# ESC_logic.net
KiCad netlist of a schematic drawn in EAGLE
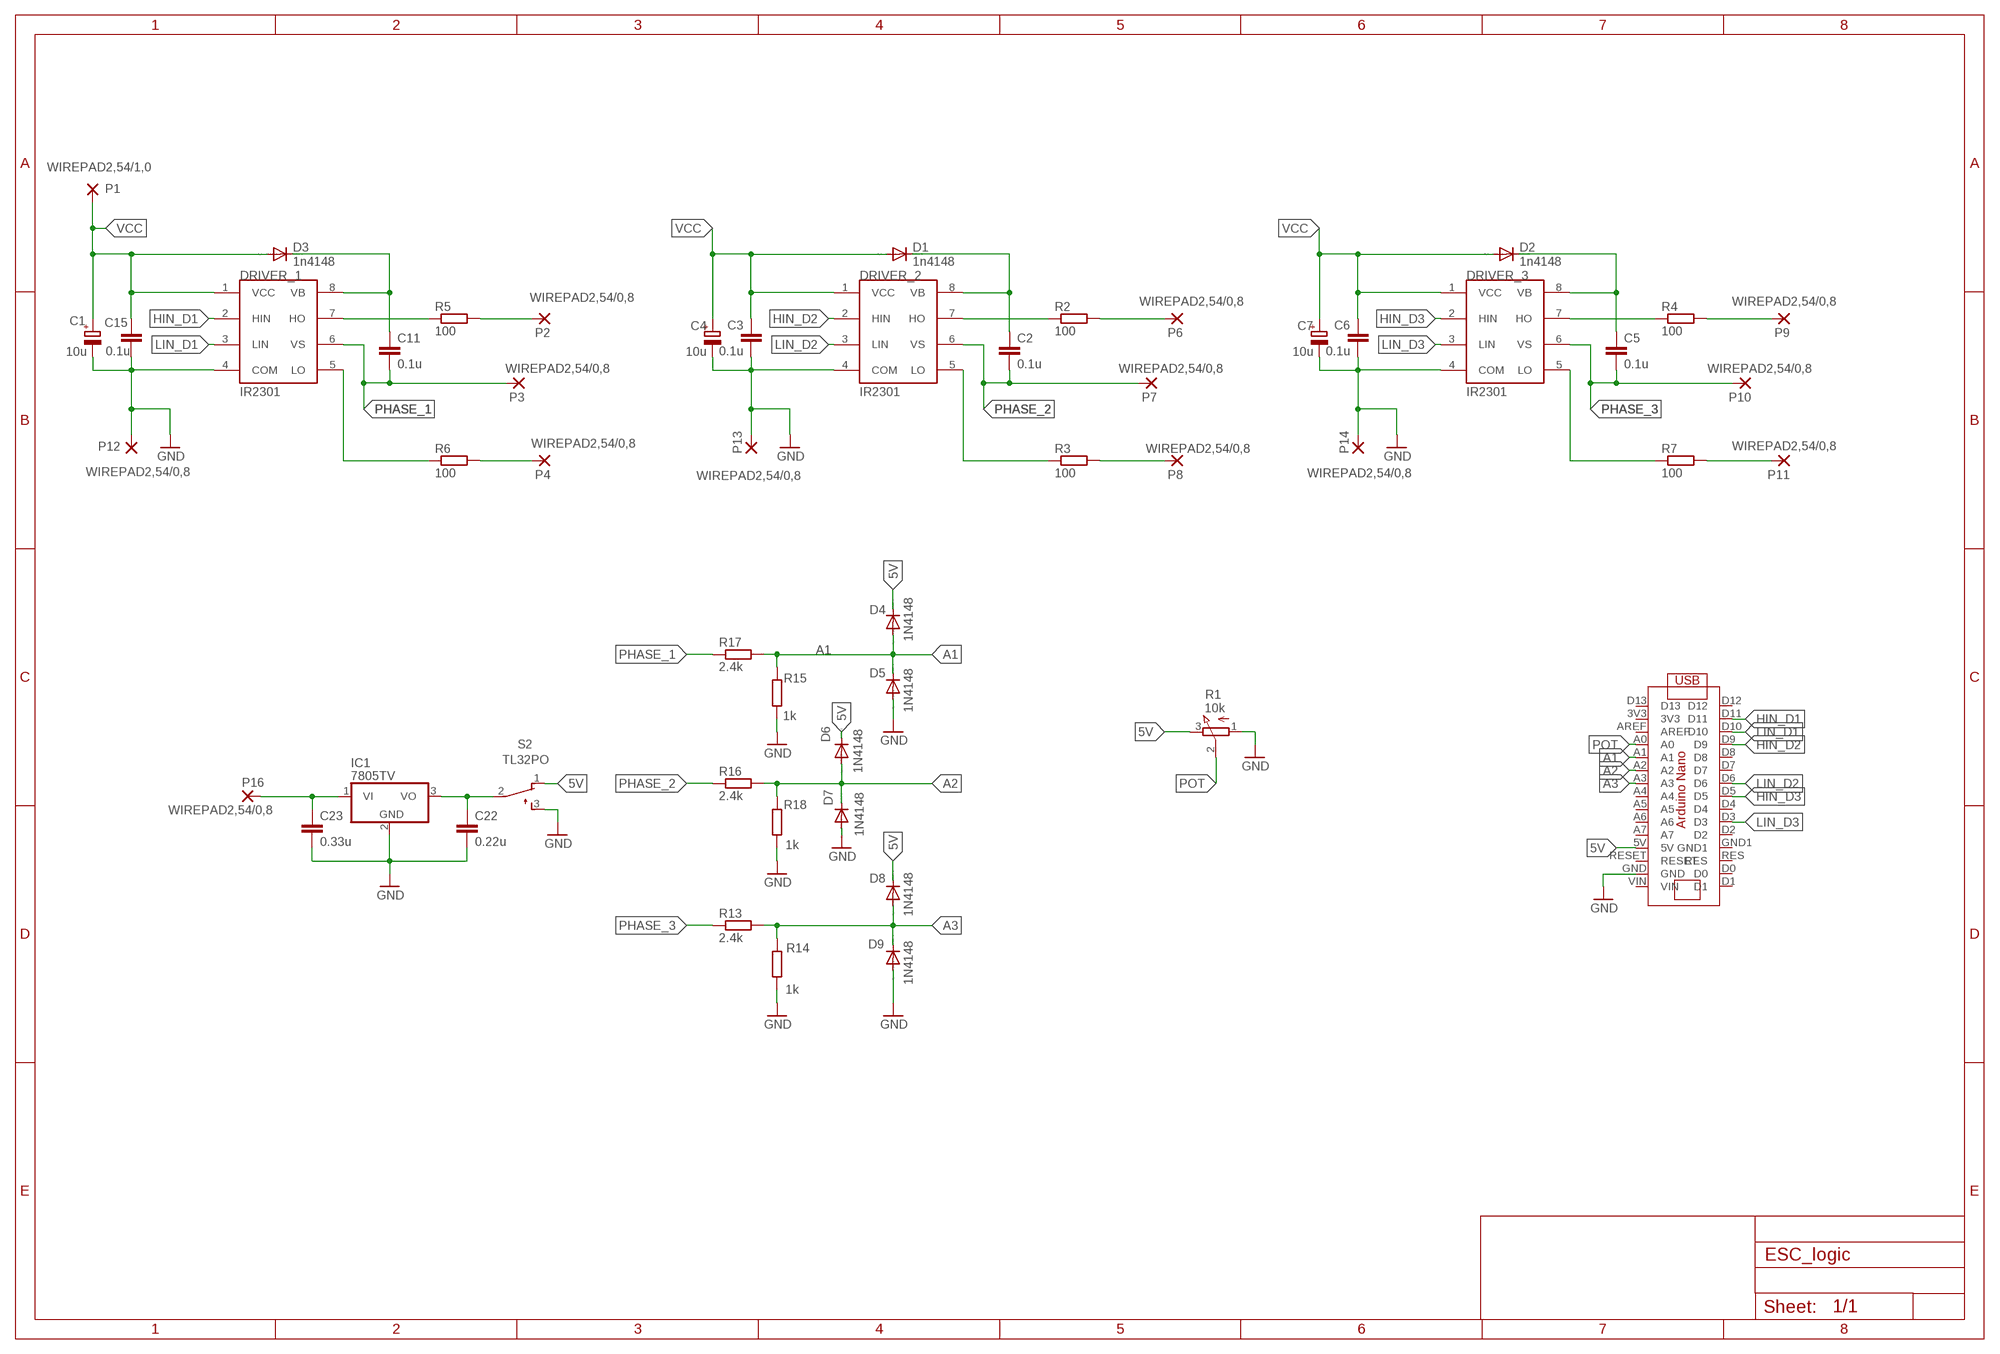
[diagram p0: schematic, sheet 1]

(export (version "E")
  (design (tool "Eeschema 10.0.6"))
  (components
    (comp (ref "C1")
      (value "10u")
      (footprint "eagle-import:153CLV-0605")
      (libsource (lib "eagle-import") (part "CPOL-EU153CLV-0605"))
    )
    (comp (ref "C2")
      (value "0.1u")
      (footprint "eagle-import:C1206")
      (libsource (lib "eagle-import") (part "CC1206"))
    )
    (comp (ref "C3")
      (value "0.1u")
      (footprint "eagle-import:C1206")
      (libsource (lib "eagle-import") (part "CC1206"))
    )
    (comp (ref "C4")
      (value "10u")
      (footprint "eagle-import:153CLV-0605")
      (libsource (lib "eagle-import") (part "CPOL-EU153CLV-0605"))
    )
    (comp (ref "C5")
      (value "0.1u")
      (footprint "eagle-import:C1206")
      (libsource (lib "eagle-import") (part "CC1206"))
    )
    (comp (ref "C6")
      (value "0.1u")
      (footprint "eagle-import:C1206")
      (libsource (lib "eagle-import") (part "CC1206"))
    )
    (comp (ref "C7")
      (value "10u")
      (footprint "eagle-import:153CLV-0605")
      (libsource (lib "eagle-import") (part "CPOL-EU153CLV-0605"))
    )
    (comp (ref "C11")
      (value "0.1u")
      (footprint "eagle-import:C1206")
      (libsource (lib "eagle-import") (part "CC1206"))
    )
    (comp (ref "C15")
      (value "0.1u")
      (footprint "eagle-import:C1206")
      (libsource (lib "eagle-import") (part "CC1206"))
    )
    (comp (ref "C22")
      (value "0.22u")
      (footprint "eagle-import:C1206")
      (libsource (lib "eagle-import") (part "CC1206"))
    )
    (comp (ref "C23")
      (value "0.33u")
      (footprint "eagle-import:C1206")
      (libsource (lib "eagle-import") (part "CC1206"))
    )
    (comp (ref "D1")
      (value "1n4148")
      (footprint "eagle-import:DO41-10")
      (libsource (lib "eagle-import") (part "DIODE-DO41-10"))
    )
    (comp (ref "D2")
      (value "1n4148")
      (footprint "eagle-import:DO41-10")
      (libsource (lib "eagle-import") (part "DIODE-DO41-10"))
    )
    (comp (ref "D3")
      (value "1n4148")
      (footprint "eagle-import:DO41-10")
      (libsource (lib "eagle-import") (part "DIODE-DO41-10"))
    )
    (comp (ref "D4")
      (value "1N4148")
      (footprint "eagle-import:DO41-10")
      (libsource (lib "eagle-import") (part "DIODE-DO41-10"))
    )
    (comp (ref "D5")
      (value "1N4148")
      (footprint "eagle-import:DO41-10")
      (libsource (lib "eagle-import") (part "DIODE-DO41-10"))
    )
    (comp (ref "D6")
      (value "1N4148")
      (footprint "eagle-import:DO41-10")
      (libsource (lib "eagle-import") (part "DIODE-DO41-10"))
    )
    (comp (ref "D7")
      (value "1N4148")
      (footprint "eagle-import:DO41-10")
      (libsource (lib "eagle-import") (part "DIODE-DO41-10"))
    )
    (comp (ref "D8")
      (value "1N4148")
      (footprint "eagle-import:DO41-10")
      (libsource (lib "eagle-import") (part "DIODE-DO41-10"))
    )
    (comp (ref "D9")
      (value "1N4148")
      (footprint "eagle-import:DO41-10")
      (libsource (lib "eagle-import") (part "DIODE-DO41-10"))
    )
    (comp (ref "DRIVER_1")
      (value "IR2301")
      (footprint "eagle-import:DIL08")
      (fields (field (name "MF") "Infineon"))
      (libsource (lib "eagle-import") (part "IR2301"))
    )
    (comp (ref "DRIVER_2")
      (value "IR2301")
      (footprint "eagle-import:DIL08")
      (fields (field (name "MF") "Infineon"))
      (libsource (lib "eagle-import") (part "IR2301"))
    )
    (comp (ref "DRIVER_3")
      (value "IR2301")
      (footprint "eagle-import:DIL08")
      (fields (field (name "MF") "Infineon"))
      (libsource (lib "eagle-import") (part "IR2301"))
    )
    (comp (ref "IC1")
      (value "7805TV")
      (footprint "eagle-import:TO220V")
      (libsource (lib "eagle-import") (part "78TV05"))
    )
    (comp (ref "P1")
      (value "WIREPAD2,54/1,0")
      (footprint "eagle-import:2,54_1,0")
      (libsource (lib "eagle-import") (part "WIREPAD2,54/1,0"))
    )
    (comp (ref "P2")
      (value "WIREPAD2,54/0,8")
      (footprint "eagle-import:2,54_0,8")
      (libsource (lib "eagle-import") (part "WIREPAD2,54/0,8"))
    )
    (comp (ref "P3")
      (value "WIREPAD2,54/0,8")
      (footprint "eagle-import:2,54_0,8")
      (libsource (lib "eagle-import") (part "WIREPAD2,54/0,8"))
    )
    (comp (ref "P4")
      (value "WIREPAD2,54/0,8")
      (footprint "eagle-import:2,54_0,8")
      (libsource (lib "eagle-import") (part "WIREPAD2,54/0,8"))
    )
    (comp (ref "P6")
      (value "WIREPAD2,54/0,8")
      (footprint "eagle-import:2,54_0,8")
      (libsource (lib "eagle-import") (part "WIREPAD2,54/0,8"))
    )
    (comp (ref "P7")
      (value "WIREPAD2,54/0,8")
      (footprint "eagle-import:2,54_0,8")
      (libsource (lib "eagle-import") (part "WIREPAD2,54/0,8"))
    )
    (comp (ref "P8")
      (value "WIREPAD2,54/0,8")
      (footprint "eagle-import:2,54_0,8")
      (libsource (lib "eagle-import") (part "WIREPAD2,54/0,8"))
    )
    (comp (ref "P9")
      (value "WIREPAD2,54/0,8")
      (footprint "eagle-import:2,54_0,8")
      (libsource (lib "eagle-import") (part "WIREPAD2,54/0,8"))
    )
    (comp (ref "P10")
      (value "WIREPAD2,54/0,8")
      (footprint "eagle-import:2,54_0,8")
      (libsource (lib "eagle-import") (part "WIREPAD2,54/0,8"))
    )
    (comp (ref "P11")
      (value "WIREPAD2,54/0,8")
      (footprint "eagle-import:2,54_0,8")
      (libsource (lib "eagle-import") (part "WIREPAD2,54/0,8"))
    )
    (comp (ref "P12")
      (value "WIREPAD2,54/0,8")
      (footprint "eagle-import:2,54_0,8")
      (libsource (lib "eagle-import") (part "WIREPAD2,54/0,8"))
    )
    (comp (ref "P13")
      (value "WIREPAD2,54/0,8")
      (footprint "eagle-import:2,54_0,8")
      (libsource (lib "eagle-import") (part "WIREPAD2,54/0,8"))
    )
    (comp (ref "P14")
      (value "WIREPAD2,54/0,8")
      (footprint "eagle-import:2,54_0,8")
      (libsource (lib "eagle-import") (part "WIREPAD2,54/0,8"))
    )
    (comp (ref "P16")
      (value "WIREPAD2,54/0,8")
      (footprint "eagle-import:2,54_0,8")
      (libsource (lib "eagle-import") (part "WIREPAD2,54/0,8"))
    )
    (comp (ref "R1")
      (value "10k")
      (footprint "eagle-import:3RP_1610N")
      (libsource (lib "eagle-import") (part "3RP/1610N"))
    )
    (comp (ref "R2")
      (value "100")
      (footprint "eagle-import:R1206")
      (libsource (lib "eagle-import") (part "R-EU_R1206"))
    )
    (comp (ref "R3")
      (value "100")
      (footprint "eagle-import:R1206")
      (libsource (lib "eagle-import") (part "R-EU_R1206"))
    )
    (comp (ref "R4")
      (value "100")
      (footprint "eagle-import:R1206")
      (libsource (lib "eagle-import") (part "R-EU_R1206"))
    )
    (comp (ref "R5")
      (value "100")
      (footprint "eagle-import:R1206")
      (libsource (lib "eagle-import") (part "R-EU_R1206"))
    )
    (comp (ref "R6")
      (value "100")
      (footprint "eagle-import:R1206")
      (libsource (lib "eagle-import") (part "R-EU_R1206"))
    )
    (comp (ref "R7")
      (value "100")
      (footprint "eagle-import:R1206")
      (libsource (lib "eagle-import") (part "R-EU_R1206"))
    )
    (comp (ref "R13")
      (value "2.4k")
      (footprint "eagle-import:R1206")
      (libsource (lib "eagle-import") (part "R-EU_R1206"))
    )
    (comp (ref "R14")
      (value "1k")
      (footprint "eagle-import:R1206")
      (libsource (lib "eagle-import") (part "R-EU_R1206"))
    )
    (comp (ref "R15")
      (value "1k")
      (footprint "eagle-import:R1206")
      (libsource (lib "eagle-import") (part "R-EU_R1206"))
    )
    (comp (ref "R16")
      (value "2.4k")
      (footprint "eagle-import:R1206")
      (libsource (lib "eagle-import") (part "R-EU_R1206"))
    )
    (comp (ref "R17")
      (value "2.4k")
      (footprint "eagle-import:R1206")
      (libsource (lib "eagle-import") (part "R-EU_R1206"))
    )
    (comp (ref "R18")
      (value "1k")
      (footprint "eagle-import:R1206")
      (libsource (lib "eagle-import") (part "R-EU_R1206"))
    )
    (comp (ref "S2")
      (value "TL32PO")
      (footprint "eagle-import:TL3XPO")
      (libsource (lib "eagle-import") (part "TL32PO"))
    )
    (comp (ref "U$7")
      (value "ARDUINO-NANO")
      (footprint "eagle-import:ARDUINO-NANO")
      (libsource (lib "eagle-import") (part "ARDUINO-NANO"))
    )
  )
  (nets
    (net (code "1") (name "5V") (class "Default")
      (node (ref "D4") (pin "C") (pinfunction "C_C") (pintype "passive"))
      (node (ref "D6") (pin "C") (pinfunction "C_C") (pintype "passive"))
      (node (ref "D8") (pin "C") (pinfunction "C_C") (pintype "passive"))
      (node (ref "R1") (pin "3") (pinfunction "E_3") (pintype "passive"))
      (node (ref "S2") (pin "1") (pinfunction "O_1") (pintype "passive"))
      (node (ref "U$7") (pin "5V") (pinfunction "5V_5V") (pintype "bidirectional"))
    )
    (net (code "2") (name "A1") (class "Default")
      (node (ref "D4") (pin "A") (pinfunction "A_A") (pintype "passive"))
      (node (ref "D5") (pin "C") (pinfunction "C_C") (pintype "passive"))
      (node (ref "R15") (pin "2") (pinfunction "2_2") (pintype "bidirectional"))
      (node (ref "R17") (pin "2") (pinfunction "2_2") (pintype "bidirectional"))
      (node (ref "U$7") (pin "A1") (pinfunction "A1_A1") (pintype "bidirectional"))
    )
    (net (code "3") (name "A2") (class "Default")
      (node (ref "D6") (pin "A") (pinfunction "A_A") (pintype "passive"))
      (node (ref "D7") (pin "C") (pinfunction "C_C") (pintype "passive"))
      (node (ref "R16") (pin "2") (pinfunction "2_2") (pintype "bidirectional"))
      (node (ref "R18") (pin "2") (pinfunction "2_2") (pintype "bidirectional"))
      (node (ref "U$7") (pin "A2") (pinfunction "A2_A2") (pintype "bidirectional"))
    )
    (net (code "4") (name "A3") (class "Default")
      (node (ref "D8") (pin "A") (pinfunction "A_A") (pintype "passive"))
      (node (ref "D9") (pin "C") (pinfunction "C_C") (pintype "passive"))
      (node (ref "R13") (pin "2") (pinfunction "2_2") (pintype "bidirectional"))
      (node (ref "R14") (pin "2") (pinfunction "2_2") (pintype "bidirectional"))
      (node (ref "U$7") (pin "A3") (pinfunction "A3_A3") (pintype "bidirectional"))
    )
    (net (code "5") (name "GND") (class "Default")
      (node (ref "C1") (pin "-") (pinfunction "-_-") (pintype "passive"))
      (node (ref "C15") (pin "2") (pinfunction "2_2") (pintype "passive"))
      (node (ref "C22") (pin "2") (pinfunction "2_2") (pintype "passive"))
      (node (ref "C23") (pin "2") (pinfunction "2_2") (pintype "passive"))
      (node (ref "C3") (pin "2") (pinfunction "2_2") (pintype "passive"))
      (node (ref "C4") (pin "-") (pinfunction "-_-") (pintype "passive"))
      (node (ref "C6") (pin "2") (pinfunction "2_2") (pintype "passive"))
      (node (ref "C7") (pin "-") (pinfunction "-_-") (pintype "passive"))
      (node (ref "D5") (pin "A") (pinfunction "A_A") (pintype "passive"))
      (node (ref "D7") (pin "A") (pinfunction "A_A") (pintype "passive"))
      (node (ref "D9") (pin "A") (pinfunction "A_A") (pintype "passive"))
      (node (ref "DRIVER_1") (pin "4") (pinfunction "COM_4") (pintype "power_in"))
      (node (ref "DRIVER_2") (pin "4") (pinfunction "COM_4") (pintype "power_in"))
      (node (ref "DRIVER_3") (pin "4") (pinfunction "COM_4") (pintype "power_in"))
      (node (ref "IC1") (pin "2") (pinfunction "GND_2") (pintype "passive"))
      (node (ref "P12") (pin "1") (pinfunction "P_1") (pintype "passive"))
      (node (ref "P13") (pin "1") (pinfunction "P_1") (pintype "passive"))
      (node (ref "P14") (pin "1") (pinfunction "P_1") (pintype "passive"))
      (node (ref "R1") (pin "1") (pinfunction "A_1") (pintype "passive"))
      (node (ref "R14") (pin "1") (pinfunction "1_1") (pintype "bidirectional"))
      (node (ref "R15") (pin "1") (pinfunction "1_1") (pintype "bidirectional"))
      (node (ref "R18") (pin "1") (pinfunction "1_1") (pintype "bidirectional"))
      (node (ref "S2") (pin "3") (pinfunction "S_3") (pintype "passive"))
      (node (ref "U$7") (pin "GND") (pinfunction "GND_GND") (pintype "bidirectional"))
    )
    (net (code "6") (name "HIN_D1") (class "Default")
      (node (ref "DRIVER_1") (pin "2") (pinfunction "HIN_2") (pintype "input"))
      (node (ref "U$7") (pin "D11") (pinfunction "D11_D11") (pintype "bidirectional"))
    )
    (net (code "7") (name "HIN_D2") (class "Default")
      (node (ref "DRIVER_2") (pin "2") (pinfunction "HIN_2") (pintype "input"))
      (node (ref "U$7") (pin "D9") (pinfunction "D9_D9") (pintype "bidirectional"))
    )
    (net (code "8") (name "HIN_D3") (class "Default")
      (node (ref "DRIVER_3") (pin "2") (pinfunction "HIN_2") (pintype "input"))
      (node (ref "U$7") (pin "D5") (pinfunction "D5_D5") (pintype "bidirectional"))
    )
    (net (code "9") (name "LIN_D1") (class "Default")
      (node (ref "DRIVER_1") (pin "3") (pinfunction "LIN_3") (pintype "input"))
      (node (ref "U$7") (pin "D10") (pinfunction "D10_D10") (pintype "bidirectional"))
    )
    (net (code "10") (name "LIN_D2") (class "Default")
      (node (ref "DRIVER_2") (pin "3") (pinfunction "LIN_3") (pintype "input"))
      (node (ref "U$7") (pin "D6") (pinfunction "D6_D6") (pintype "bidirectional"))
    )
    (net (code "11") (name "LIN_D3") (class "Default")
      (node (ref "DRIVER_3") (pin "3") (pinfunction "LIN_3") (pintype "input"))
      (node (ref "U$7") (pin "D3") (pinfunction "D3_D3") (pintype "bidirectional"))
    )
    (net (code "12") (name "Net-(DRIVER_1-HO)") (class "Default")
      (node (ref "DRIVER_1") (pin "7") (pinfunction "HO_7") (pintype "output"))
      (node (ref "R5") (pin "1") (pinfunction "1_1") (pintype "bidirectional"))
    )
    (net (code "13") (name "Net-(DRIVER_1-LO)") (class "Default")
      (node (ref "DRIVER_1") (pin "5") (pinfunction "LO_5") (pintype "output"))
      (node (ref "R6") (pin "1") (pinfunction "1_1") (pintype "bidirectional"))
    )
    (net (code "14") (name "Net-(DRIVER_1-VB)") (class "Default")
      (node (ref "C11") (pin "1") (pinfunction "1_1") (pintype "passive"))
      (node (ref "D3") (pin "C") (pinfunction "C_C") (pintype "passive"))
      (node (ref "DRIVER_1") (pin "8") (pinfunction "VB_8") (pintype "power_in"))
    )
    (net (code "15") (name "Net-(DRIVER_2-HO)") (class "Default")
      (node (ref "DRIVER_2") (pin "7") (pinfunction "HO_7") (pintype "output"))
      (node (ref "R2") (pin "1") (pinfunction "1_1") (pintype "bidirectional"))
    )
    (net (code "16") (name "Net-(DRIVER_2-LO)") (class "Default")
      (node (ref "DRIVER_2") (pin "5") (pinfunction "LO_5") (pintype "output"))
      (node (ref "R3") (pin "1") (pinfunction "1_1") (pintype "bidirectional"))
    )
    (net (code "17") (name "Net-(DRIVER_2-VB)") (class "Default")
      (node (ref "C2") (pin "1") (pinfunction "1_1") (pintype "passive"))
      (node (ref "D1") (pin "C") (pinfunction "C_C") (pintype "passive"))
      (node (ref "DRIVER_2") (pin "8") (pinfunction "VB_8") (pintype "power_in"))
    )
    (net (code "18") (name "Net-(DRIVER_3-HO)") (class "Default")
      (node (ref "DRIVER_3") (pin "7") (pinfunction "HO_7") (pintype "output"))
      (node (ref "R4") (pin "1") (pinfunction "1_1") (pintype "bidirectional"))
    )
    (net (code "19") (name "Net-(DRIVER_3-LO)") (class "Default")
      (node (ref "DRIVER_3") (pin "5") (pinfunction "LO_5") (pintype "output"))
      (node (ref "R7") (pin "1") (pinfunction "1_1") (pintype "bidirectional"))
    )
    (net (code "20") (name "Net-(DRIVER_3-VB)") (class "Default")
      (node (ref "C5") (pin "1") (pinfunction "1_1") (pintype "passive"))
      (node (ref "D2") (pin "C") (pinfunction "C_C") (pintype "passive"))
      (node (ref "DRIVER_3") (pin "8") (pinfunction "VB_8") (pintype "power_in"))
    )
    (net (code "21") (name "Net-(IC1-VI)") (class "Default")
      (node (ref "C23") (pin "1") (pinfunction "1_1") (pintype "passive"))
      (node (ref "IC1") (pin "1") (pinfunction "VI_1") (pintype "input"))
      (node (ref "P16") (pin "1") (pinfunction "P_1") (pintype "passive"))
    )
    (net (code "22") (name "Net-(IC1-VO)") (class "Default")
      (node (ref "C22") (pin "1") (pinfunction "1_1") (pintype "passive"))
      (node (ref "IC1") (pin "3") (pinfunction "VO_3") (pintype "passive"))
      (node (ref "S2") (pin "2") (pinfunction "P_2") (pintype "passive"))
    )
    (net (code "23") (name "Net-(P2-P)") (class "Default")
      (node (ref "P2") (pin "1") (pinfunction "P_1") (pintype "passive"))
      (node (ref "R5") (pin "2") (pinfunction "2_2") (pintype "bidirectional"))
    )
    (net (code "24") (name "Net-(P4-P)") (class "Default")
      (node (ref "P4") (pin "1") (pinfunction "P_1") (pintype "passive"))
      (node (ref "R6") (pin "2") (pinfunction "2_2") (pintype "bidirectional"))
    )
    (net (code "25") (name "Net-(P6-P)") (class "Default")
      (node (ref "P6") (pin "1") (pinfunction "P_1") (pintype "passive"))
      (node (ref "R2") (pin "2") (pinfunction "2_2") (pintype "bidirectional"))
    )
    (net (code "26") (name "Net-(P8-P)") (class "Default")
      (node (ref "P8") (pin "1") (pinfunction "P_1") (pintype "passive"))
      (node (ref "R3") (pin "2") (pinfunction "2_2") (pintype "bidirectional"))
    )
    (net (code "27") (name "Net-(P9-P)") (class "Default")
      (node (ref "P9") (pin "1") (pinfunction "P_1") (pintype "passive"))
      (node (ref "R4") (pin "2") (pinfunction "2_2") (pintype "bidirectional"))
    )
    (net (code "28") (name "Net-(P11-P)") (class "Default")
      (node (ref "P11") (pin "1") (pinfunction "P_1") (pintype "passive"))
      (node (ref "R7") (pin "2") (pinfunction "2_2") (pintype "bidirectional"))
    )
    (net (code "29") (name "PHASE_1") (class "Default")
      (node (ref "C11") (pin "2") (pinfunction "2_2") (pintype "passive"))
      (node (ref "DRIVER_1") (pin "6") (pinfunction "VS_6") (pintype "output"))
      (node (ref "P3") (pin "1") (pinfunction "P_1") (pintype "passive"))
      (node (ref "R17") (pin "1") (pinfunction "1_1") (pintype "bidirectional"))
    )
    (net (code "30") (name "PHASE_2") (class "Default")
      (node (ref "C2") (pin "2") (pinfunction "2_2") (pintype "passive"))
      (node (ref "DRIVER_2") (pin "6") (pinfunction "VS_6") (pintype "output"))
      (node (ref "P7") (pin "1") (pinfunction "P_1") (pintype "passive"))
      (node (ref "R16") (pin "1") (pinfunction "1_1") (pintype "bidirectional"))
    )
    (net (code "31") (name "PHASE_3") (class "Default")
      (node (ref "C5") (pin "2") (pinfunction "2_2") (pintype "passive"))
      (node (ref "DRIVER_3") (pin "6") (pinfunction "VS_6") (pintype "output"))
      (node (ref "P10") (pin "1") (pinfunction "P_1") (pintype "passive"))
      (node (ref "R13") (pin "1") (pinfunction "1_1") (pintype "bidirectional"))
    )
    (net (code "32") (name "POT") (class "Default")
      (node (ref "R1") (pin "2") (pinfunction "S_2") (pintype "passive"))
      (node (ref "U$7") (pin "A0") (pinfunction "A0_A0") (pintype "bidirectional"))
    )
    (net (code "33") (name "VCC") (class "Default")
      (node (ref "C1") (pin "+") (pinfunction "+_+") (pintype "passive"))
      (node (ref "C15") (pin "1") (pinfunction "1_1") (pintype "passive"))
      (node (ref "C3") (pin "1") (pinfunction "1_1") (pintype "passive"))
      (node (ref "C4") (pin "+") (pinfunction "+_+") (pintype "passive"))
      (node (ref "C6") (pin "1") (pinfunction "1_1") (pintype "passive"))
      (node (ref "C7") (pin "+") (pinfunction "+_+") (pintype "passive"))
      (node (ref "D1") (pin "A") (pinfunction "A_A") (pintype "passive"))
      (node (ref "D2") (pin "A") (pinfunction "A_A") (pintype "passive"))
      (node (ref "D3") (pin "A") (pinfunction "A_A") (pintype "passive"))
      (node (ref "DRIVER_1") (pin "1") (pinfunction "VCC_1") (pintype "power_in"))
      (node (ref "DRIVER_2") (pin "1") (pinfunction "VCC_1") (pintype "power_in"))
      (node (ref "DRIVER_3") (pin "1") (pinfunction "VCC_1") (pintype "power_in"))
      (node (ref "P1") (pin "1") (pinfunction "P_1") (pintype "passive"))
    )
    (net (code "34") (name "unconnected-(U$7-Pad3V3)") (class "Default")
      (node (ref "U$7") (pin "3V3") (pinfunction "3V3_3V3") (pintype "bidirectional"))
    )
    (net (code "35") (name "unconnected-(U$7-PadA4)") (class "Default")
      (node (ref "U$7") (pin "A4") (pinfunction "A4_A4") (pintype "bidirectional"))
    )
    (net (code "36") (name "unconnected-(U$7-PadA5)") (class "Default")
      (node (ref "U$7") (pin "A5") (pinfunction "A5_A5") (pintype "bidirectional"))
    )
    (net (code "37") (name "unconnected-(U$7-PadA6)") (class "Default")
      (node (ref "U$7") (pin "A6") (pinfunction "A6_A6") (pintype "bidirectional"))
    )
    (net (code "38") (name "unconnected-(U$7-PadA7)") (class "Default")
      (node (ref "U$7") (pin "A7") (pinfunction "A7_A7") (pintype "bidirectional"))
    )
    (net (code "39") (name "unconnected-(U$7-PadAREF)") (class "Default")
      (node (ref "U$7") (pin "AREF") (pinfunction "AREF_AREF") (pintype "bidirectional"))
    )
    (net (code "40") (name "unconnected-(U$7-PadD0)") (class "Default")
      (node (ref "U$7") (pin "D0") (pinfunction "D0_D0") (pintype "bidirectional"))
    )
    (net (code "41") (name "unconnected-(U$7-PadD1)") (class "Default")
      (node (ref "U$7") (pin "D1") (pinfunction "D1_D1") (pintype "bidirectional"))
    )
    (net (code "42") (name "unconnected-(U$7-PadD2)") (class "Default")
      (node (ref "U$7") (pin "D2") (pinfunction "D2_D2") (pintype "bidirectional"))
    )
    (net (code "43") (name "unconnected-(U$7-PadD4)") (class "Default")
      (node (ref "U$7") (pin "D4") (pinfunction "D4_D4") (pintype "bidirectional"))
    )
    (net (code "44") (name "unconnected-(U$7-PadD7)") (class "Default")
      (node (ref "U$7") (pin "D7") (pinfunction "D7_D7") (pintype "bidirectional"))
    )
    (net (code "45") (name "unconnected-(U$7-PadD8)") (class "Default")
      (node (ref "U$7") (pin "D8") (pinfunction "D8_D8") (pintype "bidirectional"))
    )
    (net (code "46") (name "unconnected-(U$7-PadD12)") (class "Default")
      (node (ref "U$7") (pin "D12") (pinfunction "D12_D12") (pintype "bidirectional"))
    )
    (net (code "47") (name "unconnected-(U$7-PadD13)") (class "Default")
      (node (ref "U$7") (pin "D13") (pinfunction "D13_D13") (pintype "bidirectional"))
    )
    (net (code "48") (name "unconnected-(U$7-PadGND1)") (class "Default")
      (node (ref "U$7") (pin "GND1") (pinfunction "GND1_GND1") (pintype "bidirectional"))
    )
    (net (code "49") (name "unconnected-(U$7-PadRES)") (class "Default")
      (node (ref "U$7") (pin "RES") (pinfunction "RES_RES") (pintype "bidirectional"))
    )
    (net (code "50") (name "unconnected-(U$7-PadRESET)") (class "Default")
      (node (ref "U$7") (pin "RESET") (pinfunction "RESET_RESET") (pintype "bidirectional"))
    )
    (net (code "51") (name "unconnected-(U$7-PadVIN)") (class "Default")
      (node (ref "U$7") (pin "VIN") (pinfunction "VIN_VIN") (pintype "bidirectional"))
    )
  )
)
